# srm20metal.net
KiCad netlist of a schematic drawn in EAGLE
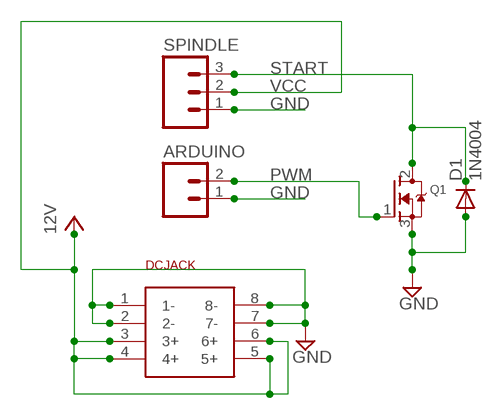
[diagram p0: schematic, sheet 1]

(export (version "E")
  (design (tool "Eeschema 10.0.6"))
  (components
    (comp (ref "ARDUINO")
      (value "M02PTH")
      (footprint "eagle-import:1X02")
      (libsource (lib "eagle-import") (part "M02PTH"))
    )
    (comp (ref "D1")
      (value "1N4004")
      (footprint "eagle-import:DO41-10")
      (libsource (lib "eagle-import") (part "1N4004"))
    )
    (comp (ref "Q1")
      (value "MOSFET-NGDS_TO220V")
      (footprint "eagle-import:TO220V")
      (libsource (lib "eagle-import") (part "MOSFET-NGDS_TO220V"))
    )
    (comp (ref "SPINDLE")
      (value "M03PTH")
      (footprint "eagle-import:1X03")
      (libsource (lib "eagle-import") (part "M03PTH"))
    )
    (comp (ref "U$1")
      (value "DCJACK")
      (footprint "eagle-import:DIPKIT")
      (libsource (lib "eagle-import") (part "DCJACK"))
    )
  )
  (nets
    (net (code "1") (name "/PWM") (class "Default")
      (node (ref "ARDUINO") (pin "2") (pinfunction "2_2") (pintype "passive"))
      (node (ref "Q1") (pin "1") (pinfunction "G_1") (pintype "bidirectional"))
    )
    (net (code "2") (name "/START") (class "Default")
      (node (ref "D1") (pin "C") (pinfunction "C_C") (pintype "passive"))
      (node (ref "Q1") (pin "2") (pinfunction "D_2") (pintype "bidirectional"))
      (node (ref "SPINDLE") (pin "3") (pinfunction "3_3") (pintype "passive"))
    )
    (net (code "3") (name "12V") (class "Default")
      (node (ref "SPINDLE") (pin "2") (pinfunction "2_2") (pintype "passive"))
      (node (ref "U$1") (pin "3") (pinfunction "3+_3") (pintype "bidirectional"))
      (node (ref "U$1") (pin "4") (pinfunction "4+_4") (pintype "bidirectional"))
      (node (ref "U$1") (pin "5") (pinfunction "5+_5") (pintype "bidirectional"))
      (node (ref "U$1") (pin "6") (pinfunction "6+_6") (pintype "bidirectional"))
    )
    (net (code "4") (name "GND") (class "Default")
      (node (ref "ARDUINO") (pin "1") (pinfunction "1_1") (pintype "passive"))
      (node (ref "D1") (pin "A") (pinfunction "A_A") (pintype "passive"))
      (node (ref "Q1") (pin "3") (pinfunction "S_3") (pintype "bidirectional"))
      (node (ref "SPINDLE") (pin "1") (pinfunction "1_1") (pintype "passive"))
      (node (ref "U$1") (pin "1") (pinfunction "1-_1") (pintype "bidirectional"))
      (node (ref "U$1") (pin "2") (pinfunction "2-_2") (pintype "bidirectional"))
      (node (ref "U$1") (pin "7") (pinfunction "7-_7") (pintype "bidirectional"))
      (node (ref "U$1") (pin "8") (pinfunction "8-_8") (pintype "bidirectional"))
    )
  )
)
